# RotaryDebouncerTop.net
KiCad netlist of a schematic drawn in Altium Designer
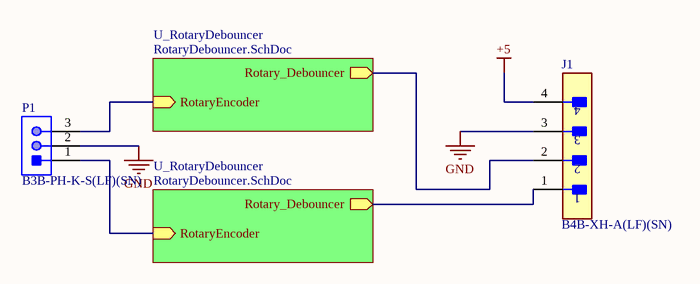
[diagram p0: RotaryDebouncerTop.SchDoc]

(export (version "E")
  (design (tool "Eeschema 10.0.6"))
  (components
    (comp (ref "J1")
      (value "B4B-XH-A(LF)(SN)")
      (footprint "FP-B4B-XH-A_LF_SN-MFG")
      (description "CONN HEADER VERT 4POS 2.5MM")
      (libsource (lib "Altium Content Vault") (part "299a8cea1bdcbc3624fe62c390fa72c"))
    )
    (comp (ref "P1")
      (value "B3B-PH-K-S(LF)(SN)")
      (footprint "JST-B3B-PH-K-S-3_V")
      (fields (field (name "MANUFACTURER") "JST"))
      (libsource (lib "Altium Content Vault") (part "CN-1P-M-R3"))
    )
  )
  (nets
    (net (code "1") (name "+5") (class "Default")
      (node (ref "J1") (pin "4") (pinfunction "4_4") (pintype "passive"))
    )
    (net (code "2") (name "/RotaryEncoder") (class "Default")
      (node (ref "P1") (pin "1") (pinfunction "1_1") (pintype "passive"))
    )
    (net (code "3") (name "/RotaryEncoder_1") (class "Default")
      (node (ref "P1") (pin "3") (pinfunction "3_3") (pintype "passive"))
    )
    (net (code "4") (name "/Rotary_Debouncer") (class "Default")
      (node (ref "J1") (pin "1") (pinfunction "1_1") (pintype "passive"))
    )
    (net (code "5") (name "/Rotary_Debouncer_1") (class "Default")
      (node (ref "J1") (pin "2") (pinfunction "2_2") (pintype "passive"))
    )
    (net (code "6") (name "GND") (class "Default")
      (node (ref "J1") (pin "3") (pinfunction "3_3") (pintype "passive"))
      (node (ref "P1") (pin "2") (pinfunction "2_2") (pintype "passive"))
    )
  )
)
